# charger_module.net
KiCad netlist of a schematic drawn in Altium Designer
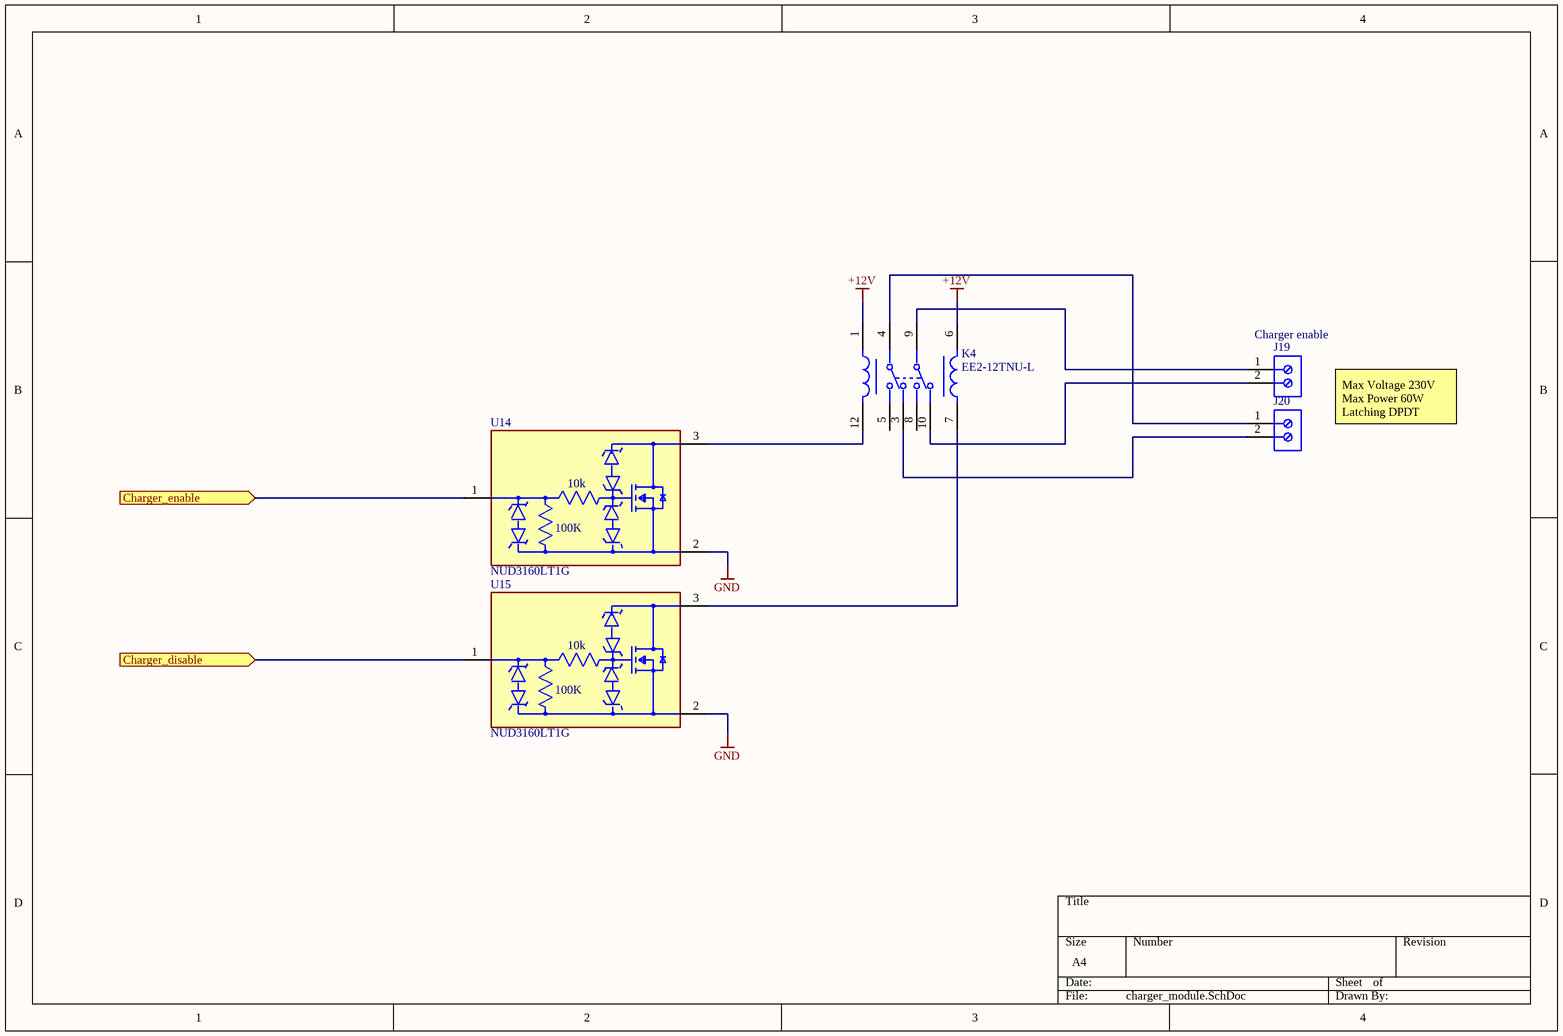
[diagram p0: charger_module.SchDoc]

(export (version "E")
  (design (tool "Eeschema 10.0.6"))
  (components
    (comp (ref "J19")
      (value "282836-2")
      (footprint "TECO-282836-2_V")
      (description "Female Header, Pitch 5 mm, 1 x 2 Position, Height 10 mm, Tail Length 3.5 mm, Rohs, Bulk")
      (fields (field (name "VOLTAGE") "300V") (field (name "MANUFACTURER") "TE Connectivity"))
      (libsource (lib "Altium Content Vault") (part "CN-1P-F-TB2"))
    )
    (comp (ref "J20")
      (value "282836-2")
      (footprint "TECO-282836-2_V")
      (description "Female Header, Pitch 5 mm, 1 x 2 Position, Height 10 mm, Tail Length 3.5 mm, Rohs, Bulk")
      (fields (field (name "VOLTAGE") "300V") (field (name "MANUFACTURER") "TE Connectivity"))
      (libsource (lib "Altium Content Vault") (part "CN-1P-F-TB2"))
    )
    (comp (ref "K4")
      (value "EE2-12TNU-L")
      (footprint "FP-EE2-12TNU-L-MFG")
      (description "RELAY GEN PURPOSE DPDT 2A 12VDC")
      (libsource (lib "Altium Content Vault") (part "a2c4c419374dacc8730513353986d3a"))
    )
    (comp (ref "U14")
      (value "NUD3160LT1G")
      (footprint "FP-318-08-MFG")
      (description "IC INDCT LOAD DRVR INDUST SOT23")
      (fields
        (field (name "OCTOPART") "https://octopart.com/nud3160lt1g-on+semiconductor-470723")
        (field (name "MANUFACTURER") "ON Semiconductor")
      )
      (libsource (lib "Altium Content Vault") (part "3565ae214b0a124fee97343a38643ca"))
    )
    (comp (ref "U15")
      (value "NUD3160LT1G")
      (footprint "FP-318-08-MFG")
      (description "IC INDCT LOAD DRVR INDUST SOT23")
      (fields
        (field (name "OCTOPART") "https://octopart.com/nud3160lt1g-on+semiconductor-470723")
        (field (name "MANUFACTURER") "ON Semiconductor")
      )
      (libsource (lib "Altium Content Vault") (part "3565ae214b0a124fee97343a38643ca"))
    )
  )
  (nets
    (net (code "1") (name "+12V") (class "Default")
      (node (ref "K4") (pin "1") (pinfunction "SET+_1") (pintype "passive"))
      (node (ref "K4") (pin "6") (pinfunction "RESET+_6") (pintype "passive"))
    )
    (net (code "2") (name "/Charger_disable") (class "Default")
      (node (ref "U15") (pin "1") (pinfunction "Gate_1") (pintype "passive"))
    )
    (net (code "3") (name "/Charger_enable") (class "Default")
      (node (ref "U14") (pin "1") (pinfunction "Gate_1") (pintype "passive"))
    )
    (net (code "4") (name "GND") (class "Default")
      (node (ref "U14") (pin "2") (pinfunction "Source_2") (pintype "passive"))
      (node (ref "U15") (pin "2") (pinfunction "Source_2") (pintype "passive"))
    )
    (net (code "5") (name "Net-(J19-Pad1)") (class "Default")
      (node (ref "J19") (pin "1") (pinfunction "1_1") (pintype "passive"))
      (node (ref "K4") (pin "9") (pinfunction "9_9") (pintype "passive"))
    )
    (net (code "6") (name "Net-(J19-Pad2)") (class "Default")
      (node (ref "J19") (pin "2") (pinfunction "2_2") (pintype "passive"))
      (node (ref "K4") (pin "10") (pinfunction "10_10") (pintype "passive"))
    )
    (net (code "7") (name "Net-(J20-Pad1)") (class "Default")
      (node (ref "J20") (pin "1") (pinfunction "1_1") (pintype "passive"))
      (node (ref "K4") (pin "4") (pinfunction "4_4") (pintype "passive"))
    )
    (net (code "8") (name "Net-(J20-Pad2)") (class "Default")
      (node (ref "J20") (pin "2") (pinfunction "2_2") (pintype "passive"))
      (node (ref "K4") (pin "3") (pinfunction "3_3") (pintype "passive"))
    )
    (net (code "9") (name "Net-(K4-RESET-)") (class "Default")
      (node (ref "K4") (pin "7") (pinfunction "RESET-_7") (pintype "passive"))
      (node (ref "U15") (pin "3") (pinfunction "Drain_3") (pintype "passive"))
    )
    (net (code "10") (name "Net-(K4-SET-)") (class "Default")
      (node (ref "K4") (pin "12") (pinfunction "SET-_12") (pintype "passive"))
      (node (ref "U14") (pin "3") (pinfunction "Drain_3") (pintype "passive"))
    )
    (net (code "11") (name "unconnected-(K4-Pad5)") (class "Default")
      (node (ref "K4") (pin "5") (pinfunction "5_5") (pintype "passive"))
    )
    (net (code "12") (name "unconnected-(K4-Pad8)") (class "Default")
      (node (ref "K4") (pin "8") (pinfunction "8_8") (pintype "passive"))
    )
  )
)
